# 3-core_board.net
KiCad netlist of a schematic drawn in Altium Designer
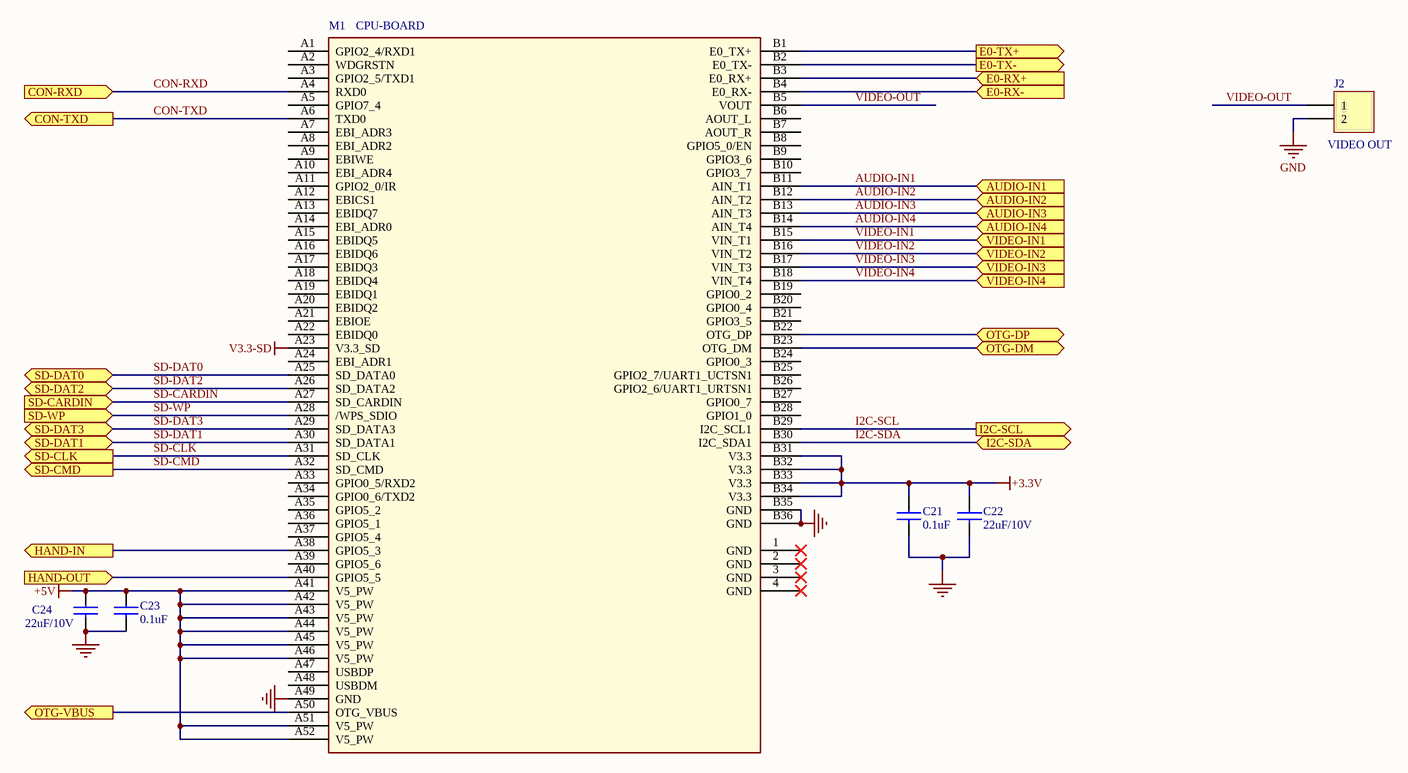
[diagram p0: 3-core_board.SchDoc]

(export (version "E")
  (design (tool "Eeschema 10.0.6"))
  (components
    (comp (ref "C21") (value "0.1uF") (libsource (lib "*") (part "CAP NP_Dup2")))
    (comp (ref "C22") (value "22uF/10V") (libsource (lib "*") (part "CAP NP_Dup2")))
    (comp (ref "C23") (value "0.1uF") (libsource (lib "*") (part "CAP NP_Dup2")))
    (comp (ref "C24") (value "22uF/10V") (libsource (lib "*") (part "CAP NP_Dup2")))
    (comp (ref "J2")
      (value "VIDEO OUT")
      (footprint "CON-2PIN")
      (description "Header, 2-Pin")
      (fields (field (name "PUBLISHER") "Altium Limited"))
      (libsource (lib "Miscellaneous Connectors") (part "Header 2"))
    )
    (comp (ref "M1") (value "CPU-BOARD") (libsource (lib "*") (part "CPU-BOARD_4")))
  )
  (nets
    (net (code "1") (name "+3.3V") (class "Default")
      (node (ref "C21") (pin "1") (pinfunction "1_1") (pintype "passive"))
      (node (ref "C22") (pin "1") (pinfunction "1_1") (pintype "passive"))
      (node (ref "M1") (pin "B31") (pinfunction "V3.3_B31") (pintype "power_in"))
      (node (ref "M1") (pin "B32") (pinfunction "V3.3_B32") (pintype "power_in"))
      (node (ref "M1") (pin "B33") (pinfunction "V3.3_B33") (pintype "power_in"))
      (node (ref "M1") (pin "B34") (pinfunction "V3.3_B34") (pintype "power_in"))
    )
    (net (code "2") (name "+5V") (class "Default")
      (node (ref "C23") (pin "1") (pinfunction "1_1") (pintype "passive"))
      (node (ref "C24") (pin "1") (pinfunction "1_1") (pintype "passive"))
      (node (ref "M1") (pin "A41") (pinfunction "V5_PW_A41") (pintype "power_in"))
      (node (ref "M1") (pin "A42") (pinfunction "V5_PW_A42") (pintype "power_in"))
      (node (ref "M1") (pin "A43") (pinfunction "V5_PW_A43") (pintype "power_in"))
      (node (ref "M1") (pin "A44") (pinfunction "V5_PW_A44") (pintype "power_in"))
      (node (ref "M1") (pin "A45") (pinfunction "V5_PW_A45") (pintype "power_in"))
      (node (ref "M1") (pin "A46") (pinfunction "V5_PW_A46") (pintype "power_in"))
      (node (ref "M1") (pin "A51") (pinfunction "V5_PW_A51") (pintype "power_in"))
      (node (ref "M1") (pin "A52") (pinfunction "V5_PW_A52") (pintype "power_in"))
    )
    (net (code "3") (name "/AUDIO-IN1") (class "Default")
      (node (ref "M1") (pin "B11") (pinfunction "AIN_T1_B11") (pintype "passive"))
    )
    (net (code "4") (name "/AUDIO-IN2") (class "Default")
      (node (ref "M1") (pin "B12") (pinfunction "AIN_T2_B12") (pintype "passive"))
    )
    (net (code "5") (name "/AUDIO-IN3") (class "Default")
      (node (ref "M1") (pin "B13") (pinfunction "AIN_T3_B13") (pintype "passive"))
    )
    (net (code "6") (name "/AUDIO-IN4") (class "Default")
      (node (ref "M1") (pin "B14") (pinfunction "AIN_T4_B14") (pintype "passive"))
    )
    (net (code "7") (name "/CON-RXD") (class "Default")
      (node (ref "M1") (pin "A4") (pinfunction "RXD0_A4") (pintype "passive"))
    )
    (net (code "8") (name "/CON-TXD") (class "Default")
      (node (ref "M1") (pin "A6") (pinfunction "TXD0_A6") (pintype "passive"))
    )
    (net (code "9") (name "/E0-RX+") (class "Default")
      (node (ref "M1") (pin "B3") (pinfunction "E0_RX+_B3") (pintype "passive"))
    )
    (net (code "10") (name "/E0-RX-") (class "Default")
      (node (ref "M1") (pin "B4") (pinfunction "E0_RX-_B4") (pintype "passive"))
    )
    (net (code "11") (name "/E0-TX+") (class "Default")
      (node (ref "M1") (pin "B1") (pinfunction "E0_TX+_B1") (pintype "passive"))
    )
    (net (code "12") (name "/E0-TX-") (class "Default")
      (node (ref "M1") (pin "B2") (pinfunction "E0_TX-_B2") (pintype "passive"))
    )
    (net (code "13") (name "/HAND-IN") (class "Default")
      (node (ref "M1") (pin "A38") (pinfunction "GPIO5_3_A38") (pintype "passive"))
    )
    (net (code "14") (name "/HAND-OUT") (class "Default")
      (node (ref "M1") (pin "A40") (pinfunction "GPIO5_5_A40") (pintype "passive"))
    )
    (net (code "15") (name "/I2C-SCL") (class "Default")
      (node (ref "M1") (pin "B29") (pinfunction "I2C_SCL1_B29") (pintype "passive"))
    )
    (net (code "16") (name "/I2C-SDA") (class "Default")
      (node (ref "M1") (pin "B30") (pinfunction "I2C_SDA1_B30") (pintype "passive"))
    )
    (net (code "17") (name "/OTG-DM") (class "Default")
      (node (ref "M1") (pin "B23") (pinfunction "OTG_DM_B23") (pintype "passive"))
    )
    (net (code "18") (name "/OTG-DP") (class "Default")
      (node (ref "M1") (pin "B22") (pinfunction "OTG_DP_B22") (pintype "passive"))
    )
    (net (code "19") (name "/OTG-VBUS") (class "Default")
      (node (ref "M1") (pin "A50") (pinfunction "OTG_VBUS_A50") (pintype "passive"))
    )
    (net (code "20") (name "/SD-CARDIN") (class "Default")
      (node (ref "M1") (pin "A27") (pinfunction "SD_CARDIN_A27") (pintype "passive"))
    )
    (net (code "21") (name "/SD-CLK") (class "Default")
      (node (ref "M1") (pin "A31") (pinfunction "SD_CLK_A31") (pintype "passive"))
    )
    (net (code "22") (name "/SD-CMD") (class "Default")
      (node (ref "M1") (pin "A32") (pinfunction "SD_CMD_A32") (pintype "passive"))
    )
    (net (code "23") (name "/SD-DAT0") (class "Default")
      (node (ref "M1") (pin "A25") (pinfunction "SD_DATA0_A25") (pintype "passive"))
    )
    (net (code "24") (name "/SD-DAT1") (class "Default")
      (node (ref "M1") (pin "A30") (pinfunction "SD_DATA1_A30") (pintype "passive"))
    )
    (net (code "25") (name "/SD-DAT2") (class "Default")
      (node (ref "M1") (pin "A26") (pinfunction "SD_DATA2_A26") (pintype "passive"))
    )
    (net (code "26") (name "/SD-DAT3") (class "Default")
      (node (ref "M1") (pin "A29") (pinfunction "SD_DATA3_A29") (pintype "passive"))
    )
    (net (code "27") (name "/SD-WP") (class "Default")
      (node (ref "M1") (pin "A28") (pinfunction "/WPS_SDIO_A28") (pintype "passive"))
    )
    (net (code "28") (name "/VIDEO-IN1") (class "Default")
      (node (ref "M1") (pin "B15") (pinfunction "VIN_T1_B15") (pintype "passive"))
    )
    (net (code "29") (name "/VIDEO-IN2") (class "Default")
      (node (ref "M1") (pin "B16") (pinfunction "VIN_T2_B16") (pintype "passive"))
    )
    (net (code "30") (name "/VIDEO-IN3") (class "Default")
      (node (ref "M1") (pin "B17") (pinfunction "VIN_T3_B17") (pintype "passive"))
    )
    (net (code "31") (name "/VIDEO-IN4") (class "Default")
      (node (ref "M1") (pin "B18") (pinfunction "VIN_T4_B18") (pintype "passive"))
    )
    (net (code "32") (name "/VIDEO-OUT") (class "Default")
      (node (ref "J2") (pin "1") (pinfunction "1_1") (pintype "passive"))
      (node (ref "M1") (pin "B5") (pinfunction "VOUT_B5") (pintype "passive"))
    )
    (net (code "33") (name "GND") (class "Default")
      (node (ref "C21") (pin "2") (pinfunction "2_2") (pintype "passive"))
      (node (ref "C22") (pin "2") (pinfunction "2_2") (pintype "passive"))
      (node (ref "C23") (pin "2") (pinfunction "2_2") (pintype "passive"))
      (node (ref "C24") (pin "2") (pinfunction "2_2") (pintype "passive"))
      (node (ref "J2") (pin "2") (pinfunction "2_2") (pintype "passive"))
      (node (ref "M1") (pin "A49") (pinfunction "GND_A49") (pintype "power_in"))
      (node (ref "M1") (pin "B35") (pinfunction "GND_B35") (pintype "power_in"))
      (node (ref "M1") (pin "B36") (pinfunction "GND_B36") (pintype "power_in"))
    )
    (net (code "34") (name "V3.3-SD") (class "Default")
      (node (ref "M1") (pin "A23") (pinfunction "V3.3_SD_A23") (pintype "passive"))
    )
    (net (code "35") (name "unconnected-(M1-AOUT_L-PadB6)") (class "Default")
      (node (ref "M1") (pin "B6") (pinfunction "AOUT_L_B6") (pintype "passive"))
    )
    (net (code "36") (name "unconnected-(M1-AOUT_R-PadB7)") (class "Default")
      (node (ref "M1") (pin "B7") (pinfunction "AOUT_R_B7") (pintype "passive"))
    )
    (net (code "37") (name "unconnected-(M1-EBICS1-PadA12)") (class "Default")
      (node (ref "M1") (pin "A12") (pinfunction "EBICS1_A12") (pintype "passive"))
    )
    (net (code "38") (name "unconnected-(M1-EBIDQ0-PadA22)") (class "Default")
      (node (ref "M1") (pin "A22") (pinfunction "EBIDQ0_A22") (pintype "passive"))
    )
    (net (code "39") (name "unconnected-(M1-EBIDQ1-PadA19)") (class "Default")
      (node (ref "M1") (pin "A19") (pinfunction "EBIDQ1_A19") (pintype "passive"))
    )
    (net (code "40") (name "unconnected-(M1-EBIDQ2-PadA20)") (class "Default")
      (node (ref "M1") (pin "A20") (pinfunction "EBIDQ2_A20") (pintype "passive"))
    )
    (net (code "41") (name "unconnected-(M1-EBIDQ3-PadA17)") (class "Default")
      (node (ref "M1") (pin "A17") (pinfunction "EBIDQ3_A17") (pintype "passive"))
    )
    (net (code "42") (name "unconnected-(M1-EBIDQ4-PadA18)") (class "Default")
      (node (ref "M1") (pin "A18") (pinfunction "EBIDQ4_A18") (pintype "passive"))
    )
    (net (code "43") (name "unconnected-(M1-EBIDQ5-PadA15)") (class "Default")
      (node (ref "M1") (pin "A15") (pinfunction "EBIDQ5_A15") (pintype "passive"))
    )
    (net (code "44") (name "unconnected-(M1-EBIDQ6-PadA16)") (class "Default")
      (node (ref "M1") (pin "A16") (pinfunction "EBIDQ6_A16") (pintype "passive"))
    )
    (net (code "45") (name "unconnected-(M1-EBIDQ7-PadA13)") (class "Default")
      (node (ref "M1") (pin "A13") (pinfunction "EBIDQ7_A13") (pintype "passive"))
    )
    (net (code "46") (name "unconnected-(M1-EBIOE-PadA21)") (class "Default")
      (node (ref "M1") (pin "A21") (pinfunction "EBIOE_A21") (pintype "passive"))
    )
    (net (code "47") (name "unconnected-(M1-EBIWE-PadA9)") (class "Default")
      (node (ref "M1") (pin "A9") (pinfunction "EBIWE_A9") (pintype "passive"))
    )
    (net (code "48") (name "unconnected-(M1-EBI_ADR0-PadA14)") (class "Default")
      (node (ref "M1") (pin "A14") (pinfunction "EBI_ADR0_A14") (pintype "passive"))
    )
    (net (code "49") (name "unconnected-(M1-EBI_ADR1-PadA24)") (class "Default")
      (node (ref "M1") (pin "A24") (pinfunction "EBI_ADR1_A24") (pintype "passive"))
    )
    (net (code "50") (name "unconnected-(M1-EBI_ADR2-PadA8)") (class "Default")
      (node (ref "M1") (pin "A8") (pinfunction "EBI_ADR2_A8") (pintype "passive"))
    )
    (net (code "51") (name "unconnected-(M1-EBI_ADR3-PadA7)") (class "Default")
      (node (ref "M1") (pin "A7") (pinfunction "EBI_ADR3_A7") (pintype "passive"))
    )
    (net (code "52") (name "unconnected-(M1-EBI_ADR4-PadA10)") (class "Default")
      (node (ref "M1") (pin "A10") (pinfunction "EBI_ADR4_A10") (pintype "passive"))
    )
    (net (code "53") (name "unconnected-(M1-GND-Pad1)") (class "Default")
      (node (ref "M1") (pin "1") (pinfunction "GND_1") (pintype "power_in+no_connect"))
    )
    (net (code "54") (name "unconnected-(M1-GND-Pad2)") (class "Default")
      (node (ref "M1") (pin "2") (pinfunction "GND_2") (pintype "power_in+no_connect"))
    )
    (net (code "55") (name "unconnected-(M1-GND-Pad3)") (class "Default")
      (node (ref "M1") (pin "3") (pinfunction "GND_3") (pintype "power_in+no_connect"))
    )
    (net (code "56") (name "unconnected-(M1-GND-Pad4)") (class "Default")
      (node (ref "M1") (pin "4") (pinfunction "GND_4") (pintype "power_in+no_connect"))
    )
    (net (code "57") (name "unconnected-(M1-GPIO0_2-PadB19)") (class "Default")
      (node (ref "M1") (pin "B19") (pinfunction "GPIO0_2_B19") (pintype "passive"))
    )
    (net (code "58") (name "unconnected-(M1-GPIO0_3-PadB24)") (class "Default")
      (node (ref "M1") (pin "B24") (pinfunction "GPIO0_3_B24") (pintype "passive"))
    )
    (net (code "59") (name "unconnected-(M1-GPIO0_4-PadB20)") (class "Default")
      (node (ref "M1") (pin "B20") (pinfunction "GPIO0_4_B20") (pintype "passive"))
    )
    (net (code "60") (name "unconnected-(M1-GPIO0_5{slash}RXD2-PadA33)") (class "Default")
      (node (ref "M1") (pin "A33") (pinfunction "GPIO0_5/RXD2_A33") (pintype "passive"))
    )
    (net (code "61") (name "unconnected-(M1-GPIO0_6{slash}TXD2-PadA34)") (class "Default")
      (node (ref "M1") (pin "A34") (pinfunction "GPIO0_6/TXD2_A34") (pintype "passive"))
    )
    (net (code "62") (name "unconnected-(M1-GPIO0_7-PadB27)") (class "Default")
      (node (ref "M1") (pin "B27") (pinfunction "GPIO0_7_B27") (pintype "passive"))
    )
    (net (code "63") (name "unconnected-(M1-GPIO1_0-PadB28)") (class "Default")
      (node (ref "M1") (pin "B28") (pinfunction "GPIO1_0_B28") (pintype "passive"))
    )
    (net (code "64") (name "unconnected-(M1-GPIO2_0{slash}IR-PadA11)") (class "Default")
      (node (ref "M1") (pin "A11") (pinfunction "GPIO2_0/IR_A11") (pintype "passive"))
    )
    (net (code "65") (name "unconnected-(M1-GPIO2_4{slash}RXD1-PadA1)") (class "Default")
      (node (ref "M1") (pin "A1") (pinfunction "GPIO2_4/RXD1_A1") (pintype "passive"))
    )
    (net (code "66") (name "unconnected-(M1-GPIO2_5{slash}TXD1-PadA3)") (class "Default")
      (node (ref "M1") (pin "A3") (pinfunction "GPIO2_5/TXD1_A3") (pintype "passive"))
    )
    (net (code "67") (name "unconnected-(M1-GPIO2_6{slash}UART1_URTSN1-PadB26)") (class "Default")
      (node (ref "M1") (pin "B26") (pinfunction "GPIO2_6/UART1_URTSN1_B26") (pintype "passive"))
    )
    (net (code "68") (name "unconnected-(M1-GPIO2_7{slash}UART1_UCTSN1-PadB25)") (class "Default")
      (node (ref "M1") (pin "B25") (pinfunction "GPIO2_7/UART1_UCTSN1_B25") (pintype "passive"))
    )
    (net (code "69") (name "unconnected-(M1-GPIO3_5-PadB21)") (class "Default")
      (node (ref "M1") (pin "B21") (pinfunction "GPIO3_5_B21") (pintype "passive"))
    )
    (net (code "70") (name "unconnected-(M1-GPIO3_6-PadB9)") (class "Default")
      (node (ref "M1") (pin "B9") (pinfunction "GPIO3_6_B9") (pintype "passive"))
    )
    (net (code "71") (name "unconnected-(M1-GPIO3_7-PadB10)") (class "Default")
      (node (ref "M1") (pin "B10") (pinfunction "GPIO3_7_B10") (pintype "passive"))
    )
    (net (code "72") (name "unconnected-(M1-GPIO5_0{slash}EN-PadB8)") (class "Default")
      (node (ref "M1") (pin "B8") (pinfunction "GPIO5_0/EN_B8") (pintype "passive"))
    )
    (net (code "73") (name "unconnected-(M1-GPIO5_1-PadA36)") (class "Default")
      (node (ref "M1") (pin "A36") (pinfunction "GPIO5_1_A36") (pintype "passive"))
    )
    (net (code "74") (name "unconnected-(M1-GPIO5_2-PadA35)") (class "Default")
      (node (ref "M1") (pin "A35") (pinfunction "GPIO5_2_A35") (pintype "passive"))
    )
    (net (code "75") (name "unconnected-(M1-GPIO5_4-PadA37)") (class "Default")
      (node (ref "M1") (pin "A37") (pinfunction "GPIO5_4_A37") (pintype "passive"))
    )
    (net (code "76") (name "unconnected-(M1-GPIO5_6-PadA39)") (class "Default")
      (node (ref "M1") (pin "A39") (pinfunction "GPIO5_6_A39") (pintype "passive"))
    )
    (net (code "77") (name "unconnected-(M1-GPIO7_4-PadA5)") (class "Default")
      (node (ref "M1") (pin "A5") (pinfunction "GPIO7_4_A5") (pintype "passive"))
    )
    (net (code "78") (name "unconnected-(M1-USBDM-PadA48)") (class "Default")
      (node (ref "M1") (pin "A48") (pinfunction "USBDM_A48") (pintype "passive"))
    )
    (net (code "79") (name "unconnected-(M1-USBDP-PadA47)") (class "Default")
      (node (ref "M1") (pin "A47") (pinfunction "USBDP_A47") (pintype "passive"))
    )
    (net (code "80") (name "unconnected-(M1-WDGRSTN-PadA2)") (class "Default")
      (node (ref "M1") (pin "A2") (pinfunction "WDGRSTN_A2") (pintype "passive"))
    )
  )
)
